# LCD.net
KiCad netlist of a schematic drawn in Altium Designer
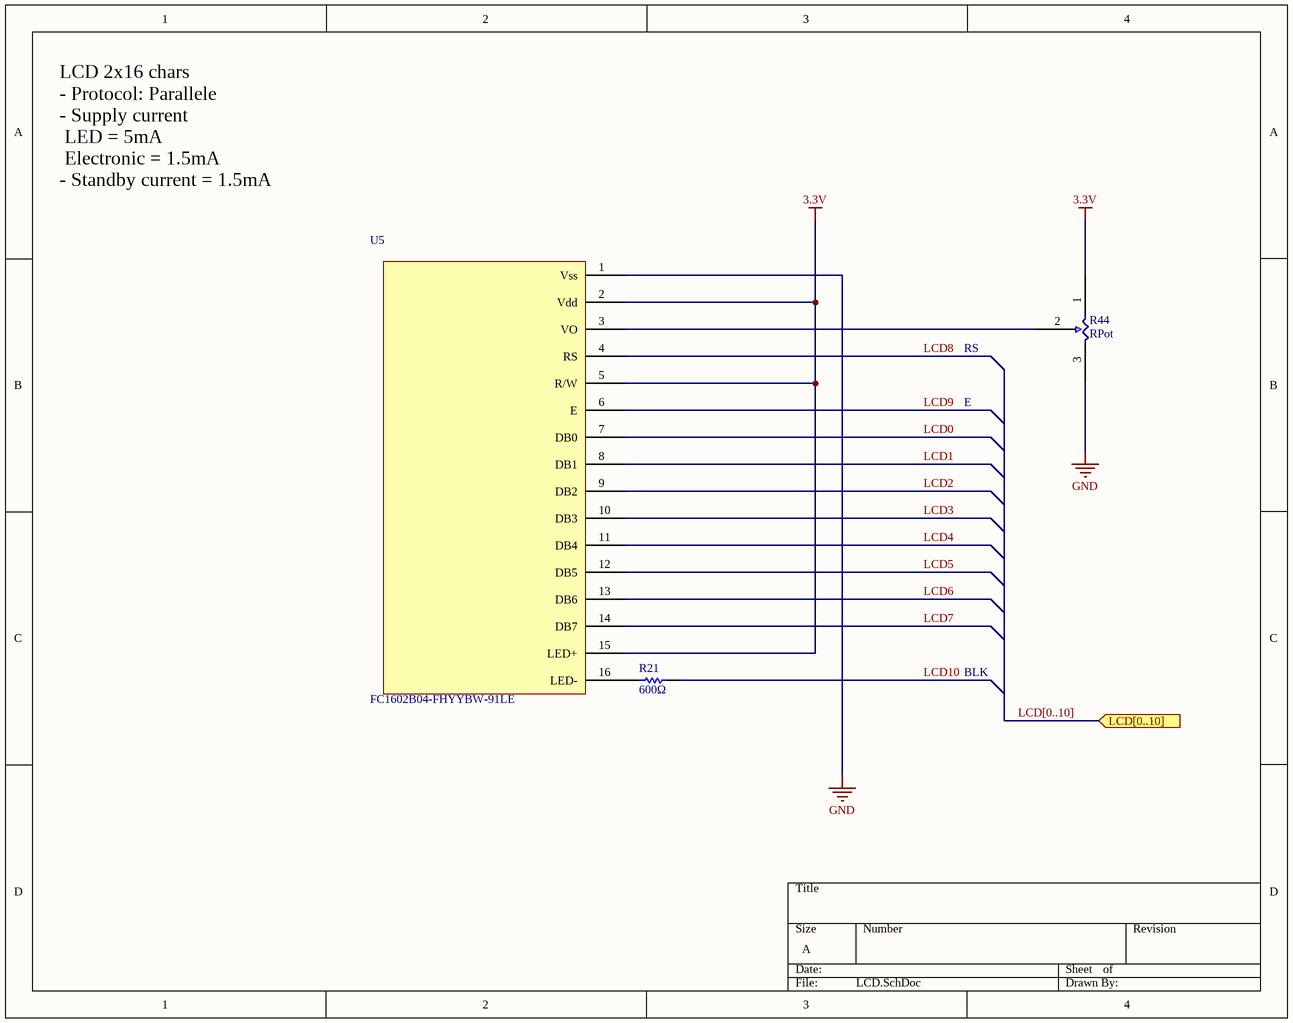
[diagram p0: LCD.SchDoc]

(export (version "E")
  (design (tool "Eeschema 10.0.6"))
  (components
    (comp (ref "R21")
      (value "600Ω")
      (footprint "R0603")
      (description "Resistor")
      (fields (field (name "MANUFACTURER") "MULTICOMP") (field (name "PUBLISHER") "Altium Limited"))
      (libsource (lib "Miscellaneous Devices") (part "Res1"))
    )
    (comp (ref "R44")
      (value "RPot")
      (footprint "POTARD")
      (description "Varistor")
      (fields (field (name "MANUFACTURER") "VISHAY"))
      (libsource (lib "Electroplant") (part "Potard"))
    )
    (comp (ref "U5")
      (value "FC1602B04-FHYYBW-91LE")
      (footprint "FC1602B04-FHYYBW-91LE")
      (description "LCD")
      (fields (field (name "MANUFACTURER") "FORDATA"))
      (libsource (lib "Electroplant") (part "FC1602B04-FHYYBW-91LE"))
    )
  )
  (nets
    (net (code "1") (name "/LCD0") (class "Default")
      (node (ref "U5") (pin "7") (pinfunction "DB0_7") (pintype "passive"))
    )
    (net (code "2") (name "/LCD1") (class "Default")
      (node (ref "U5") (pin "8") (pinfunction "DB1_8") (pintype "passive"))
    )
    (net (code "3") (name "/LCD2") (class "Default")
      (node (ref "U5") (pin "9") (pinfunction "DB2_9") (pintype "passive"))
    )
    (net (code "4") (name "/LCD3") (class "Default")
      (node (ref "U5") (pin "10") (pinfunction "DB3_10") (pintype "passive"))
    )
    (net (code "5") (name "/LCD4") (class "Default")
      (node (ref "U5") (pin "11") (pinfunction "DB4_11") (pintype "passive"))
    )
    (net (code "6") (name "/LCD5") (class "Default")
      (node (ref "U5") (pin "12") (pinfunction "DB5_12") (pintype "passive"))
    )
    (net (code "7") (name "/LCD6") (class "Default")
      (node (ref "U5") (pin "13") (pinfunction "DB6_13") (pintype "passive"))
    )
    (net (code "8") (name "/LCD7") (class "Default")
      (node (ref "U5") (pin "14") (pinfunction "DB7_14") (pintype "passive"))
    )
    (net (code "9") (name "/LCD8") (class "Default")
      (node (ref "U5") (pin "4") (pinfunction "RS_4") (pintype "passive"))
    )
    (net (code "10") (name "/LCD9") (class "Default")
      (node (ref "U5") (pin "6") (pinfunction "E_6") (pintype "passive"))
    )
    (net (code "11") (name "/LCD10") (class "Default")
      (node (ref "R21") (pin "2") (pinfunction "2_2") (pintype "passive"))
    )
    (net (code "13") (name "3.3V") (class "Default")
      (node (ref "R44") (pin "1") (pinfunction "1_1") (pintype "passive"))
      (node (ref "U5") (pin "15") (pinfunction "LED+_15") (pintype "passive"))
      (node (ref "U5") (pin "2") (pinfunction "Vdd_2") (pintype "passive"))
      (node (ref "U5") (pin "5") (pinfunction "R/W_5") (pintype "passive"))
    )
    (net (code "14") (name "GND") (class "Default")
      (node (ref "R44") (pin "3") (pinfunction "3_3") (pintype "passive"))
      (node (ref "U5") (pin "1") (pinfunction "Vss_1") (pintype "passive"))
    )
    (net (code "15") (name "Net-(U5-LED-)") (class "Default")
      (node (ref "R21") (pin "1") (pinfunction "1_1") (pintype "passive"))
      (node (ref "U5") (pin "16") (pinfunction "LED-_16") (pintype "passive"))
    )
    (net (code "16") (name "Net-(U5-VO)") (class "Default")
      (node (ref "R44") (pin "2") (pinfunction "2_2") (pintype "passive"))
      (node (ref "U5") (pin "3") (pinfunction "VO_3") (pintype "passive"))
    )
  )
)
